# smartGarden_Per_Rev01.net
KiCad netlist of a schematic drawn in Altium Designer
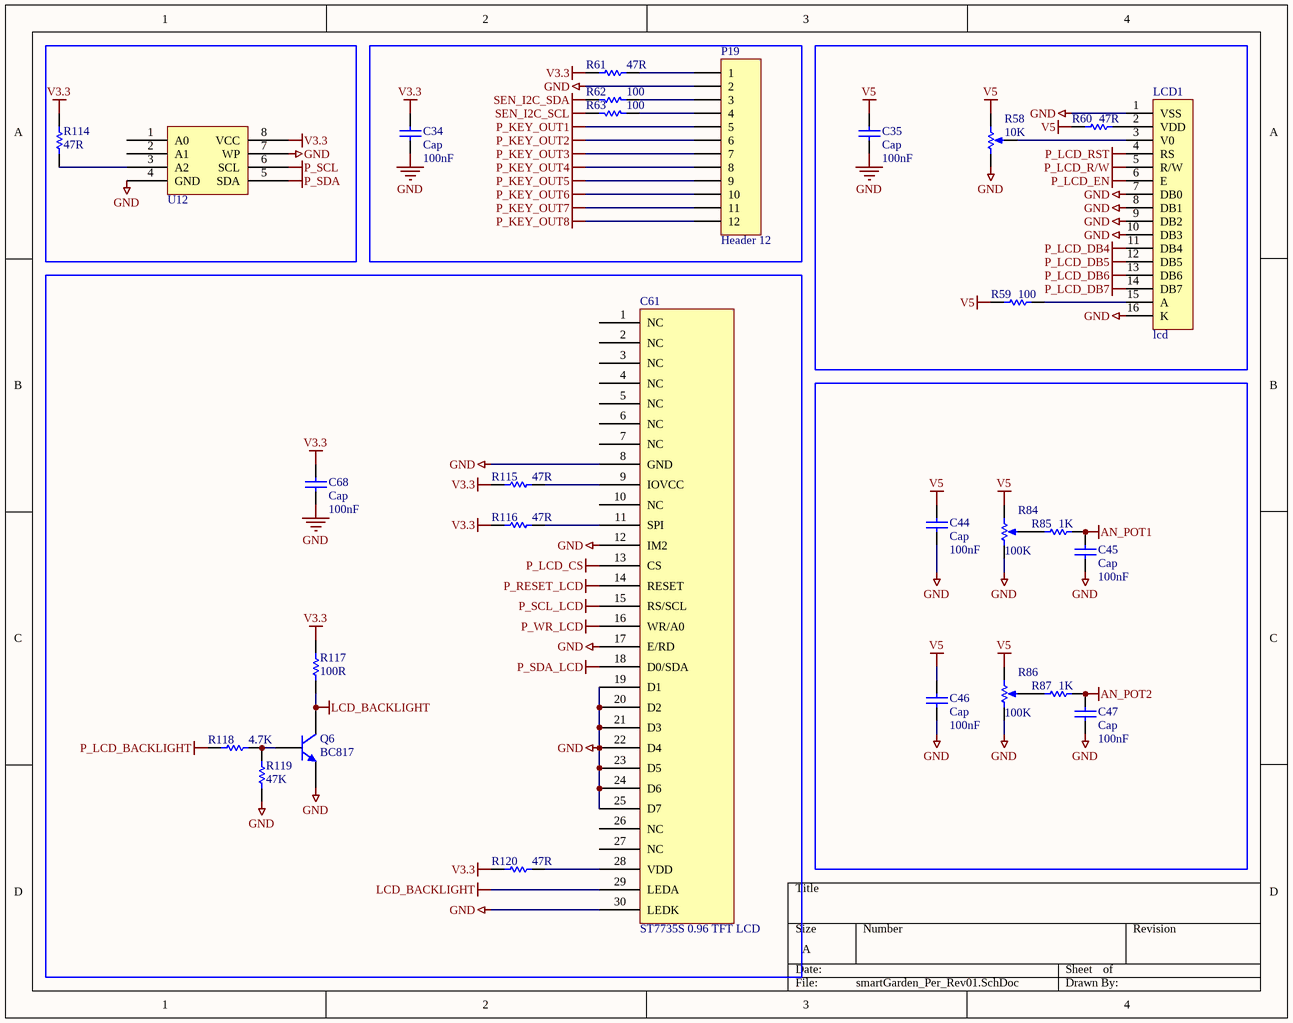
[diagram p0: smartGarden_Per_Rev01.SchDoc]

(export (version "E")
  (design (tool "Eeschema 10.0.6"))
  (components
    (comp (ref "C34")
      (value "Cap")
      (footprint "0805_smd")
      (description "Capacitor")
      (fields (field (name "ALTIUM_VALUE") "100nF") (field (name "PUBLISHER") "Altium Limited"))
      (libsource (lib "Miscellaneous Devices") (part "Cap"))
    )
    (comp (ref "C35")
      (value "Cap")
      (footprint "0805_smd")
      (description "Capacitor")
      (fields (field (name "ALTIUM_VALUE") "100nF") (field (name "PUBLISHER") "Altium Limited"))
      (libsource (lib "Miscellaneous Devices") (part "Cap"))
    )
    (comp (ref "C44")
      (value "Cap")
      (footprint "0805_smd")
      (description "Capacitor")
      (fields (field (name "ALTIUM_VALUE") "100nF") (field (name "PUBLISHER") "Altium Limited"))
      (libsource (lib "Miscellaneous Devices") (part "Cap"))
    )
    (comp (ref "C45")
      (value "Cap")
      (footprint "0805_smd")
      (description "Capacitor")
      (fields (field (name "ALTIUM_VALUE") "100nF") (field (name "PUBLISHER") "Altium Limited"))
      (libsource (lib "Miscellaneous Devices") (part "Cap"))
    )
    (comp (ref "C46")
      (value "Cap")
      (footprint "0805_smd")
      (description "Capacitor")
      (fields (field (name "ALTIUM_VALUE") "100nF") (field (name "PUBLISHER") "Altium Limited"))
      (libsource (lib "Miscellaneous Devices") (part "Cap"))
    )
    (comp (ref "C47")
      (value "Cap")
      (footprint "0805_smd")
      (description "Capacitor")
      (fields (field (name "ALTIUM_VALUE") "100nF") (field (name "PUBLISHER") "Altium Limited"))
      (libsource (lib "Miscellaneous Devices") (part "Cap"))
    )
    (comp (ref "C61")
      (value "ST7735S 0.96 TFT LCD")
      (libsource (lib "MYLib524") (part "ST7735S 0.96 TFT LCD"))
    )
    (comp (ref "C68")
      (value "Cap")
      (footprint "0805_smd")
      (description "Capacitor")
      (fields (field (name "ALTIUM_VALUE") "100nF") (field (name "PUBLISHER") "Altium Limited"))
      (libsource (lib "Miscellaneous Devices") (part "Cap"))
    )
    (comp (ref "LCD1") (value "lcd") (footprint "LCD2*16") (libsource (lib "MYLib524") (part "LCD16")))
    (comp (ref "P19")
      (value "Header 12")
      (footprint "CON12_XH")
      (description "Header, 12-Pin")
      (fields (field (name "PUBLISHER") "Altium Limited"))
      (libsource (lib "Miscellaneous Connectors") (part "Header 12"))
    )
    (comp (ref "Q6")
      (value "BC817")
      (footprint "TO-226-AA")
      (description "NPN Bipolar Transistor")
      (fields (field (name "PUBLISHER") "Altium Limited"))
      (libsource (lib "Miscellaneous Devices") (part "NPN"))
    )
    (comp (ref "R58")
      (value "10K")
      (footprint "Trimmer Pot")
      (description "Potentiometer")
      (fields (field (name "Comment") "RPot") (field (name "PUBLISHER") "Altium Limited"))
      (libsource (lib "Miscellaneous Devices") (part "RPot"))
    )
    (comp (ref "R59")
      (value "100")
      (footprint "0805_smd")
      (description "Semiconductor Resistor")
      (fields (field (name "PUBLISHER") "Altium Limited"))
      (libsource (lib "Miscellaneous Devices") (part "Res Semi"))
    )
    (comp (ref "R60")
      (value "47R")
      (footprint "0805_smd")
      (description "Semiconductor Resistor")
      (fields (field (name "PUBLISHER") "Altium Limited"))
      (libsource (lib "Miscellaneous Devices") (part "Res Semi"))
    )
    (comp (ref "R61")
      (value "47R")
      (footprint "0805_smd")
      (description "Semiconductor Resistor")
      (fields (field (name "PUBLISHER") "Altium Limited"))
      (libsource (lib "Miscellaneous Devices") (part "Res Semi"))
    )
    (comp (ref "R62")
      (value "100")
      (footprint "0805_smd")
      (description "Resistor")
      (fields (field (name "PUBLISHER") "Altium Limited"))
      (libsource (lib "Miscellaneous Devices") (part "Res1"))
    )
    (comp (ref "R63")
      (value "100")
      (footprint "0805_smd")
      (description "Resistor")
      (fields (field (name "PUBLISHER") "Altium Limited"))
      (libsource (lib "Miscellaneous Devices") (part "Res1"))
    )
    (comp (ref "R84")
      (value "100K")
      (footprint "POT_V15")
      (description "Potentiometer")
      (fields (field (name "Comment") "RPot") (field (name "PUBLISHER") "Altium Limited"))
      (libsource (lib "Miscellaneous Devices") (part "RPot"))
    )
    (comp (ref "R85")
      (value "1K")
      (footprint "0805_smd")
      (description "Semiconductor Resistor")
      (fields (field (name "PUBLISHER") "Altium Limited"))
      (libsource (lib "Miscellaneous Devices") (part "Res Semi"))
    )
    (comp (ref "R86")
      (value "100K")
      (footprint "POT_V15")
      (description "Potentiometer")
      (fields (field (name "Comment") "RPot") (field (name "PUBLISHER") "Altium Limited"))
      (libsource (lib "Miscellaneous Devices") (part "RPot"))
    )
    (comp (ref "R87")
      (value "1K")
      (footprint "0805_smd")
      (description "Semiconductor Resistor")
      (fields (field (name "PUBLISHER") "Altium Limited"))
      (libsource (lib "Miscellaneous Devices") (part "Res Semi"))
    )
    (comp (ref "R114")
      (value "47R")
      (footprint "0805_smd")
      (description "Semiconductor Resistor")
      (fields (field (name "PUBLISHER") "Altium Limited"))
      (libsource (lib "Miscellaneous Devices") (part "Res Semi"))
    )
    (comp (ref "R115")
      (value "47R")
      (footprint "0805_smd")
      (description "Semiconductor Resistor")
      (fields (field (name "PUBLISHER") "Altium Limited"))
      (libsource (lib "Miscellaneous Devices") (part "Res Semi"))
    )
    (comp (ref "R116")
      (value "47R")
      (footprint "0805_smd")
      (description "Semiconductor Resistor")
      (fields (field (name "PUBLISHER") "Altium Limited"))
      (libsource (lib "Miscellaneous Devices") (part "Res Semi"))
    )
    (comp (ref "R117")
      (value "100R")
      (footprint "0805_smd")
      (description "Semiconductor Resistor")
      (fields (field (name "PUBLISHER") "Altium Limited"))
      (libsource (lib "Miscellaneous Devices") (part "Res Semi"))
    )
    (comp (ref "R118")
      (value "4.7K")
      (footprint "0805_smd")
      (description "Semiconductor Resistor")
      (fields (field (name "PUBLISHER") "Altium Limited"))
      (libsource (lib "Miscellaneous Devices") (part "Res Semi"))
    )
    (comp (ref "R119")
      (value "47K")
      (footprint "0805_smd")
      (description "Semiconductor Resistor")
      (fields (field (name "PUBLISHER") "Altium Limited"))
      (libsource (lib "Miscellaneous Devices") (part "Res Semi"))
    )
    (comp (ref "R120")
      (value "47R")
      (footprint "0805_smd")
      (description "Semiconductor Resistor")
      (fields (field (name "PUBLISHER") "Altium Limited"))
      (libsource (lib "Miscellaneous Devices") (part "Res Semi"))
    )
    (comp (ref "U12") (value "AT24C08") (footprint "SOIC8") (libsource (lib "MYLib524") (part "AT24C08")))
  )
  (nets
    (net (code "1") (name "AN_POT1") (class "Default")
      (node (ref "C45") (pin "2") (pinfunction "2_2") (pintype "passive"))
      (node (ref "R85") (pin "1") (pinfunction "1_1") (pintype "passive"))
    )
    (net (code "2") (name "AN_POT2") (class "Default")
      (node (ref "C47") (pin "2") (pinfunction "2_2") (pintype "passive"))
      (node (ref "R87") (pin "1") (pinfunction "1_1") (pintype "passive"))
    )
    (net (code "3") (name "GND") (class "Default")
      (node (ref "C34") (pin "1") (pinfunction "1_1") (pintype "passive"))
      (node (ref "C35") (pin "1") (pinfunction "1_1") (pintype "passive"))
      (node (ref "C44") (pin "1") (pinfunction "1_1") (pintype "passive"))
      (node (ref "C45") (pin "1") (pinfunction "1_1") (pintype "passive"))
      (node (ref "C46") (pin "1") (pinfunction "1_1") (pintype "passive"))
      (node (ref "C47") (pin "1") (pinfunction "1_1") (pintype "passive"))
      (node (ref "C61") (pin "12") (pinfunction "IM2_12") (pintype "passive"))
      (node (ref "C61") (pin "17") (pinfunction "E/RD_17") (pintype "passive"))
      (node (ref "C61") (pin "19") (pinfunction "D1_19") (pintype "passive"))
      (node (ref "C61") (pin "20") (pinfunction "D2_20") (pintype "passive"))
      (node (ref "C61") (pin "21") (pinfunction "D3_21") (pintype "passive"))
      (node (ref "C61") (pin "22") (pinfunction "D4_22") (pintype "passive"))
      (node (ref "C61") (pin "23") (pinfunction "D5_23") (pintype "passive"))
      (node (ref "C61") (pin "24") (pinfunction "D6_24") (pintype "passive"))
      (node (ref "C61") (pin "25") (pinfunction "D7_25") (pintype "passive"))
      (node (ref "C61") (pin "30") (pinfunction "LEDK_30") (pintype "passive"))
      (node (ref "C61") (pin "8") (pinfunction "GND_8") (pintype "passive"))
      (node (ref "C68") (pin "1") (pinfunction "1_1") (pintype "passive"))
      (node (ref "LCD1") (pin "1") (pinfunction "VSS_1") (pintype "passive"))
      (node (ref "LCD1") (pin "10") (pinfunction "DB3_10") (pintype "passive"))
      (node (ref "LCD1") (pin "16") (pinfunction "K_16") (pintype "passive"))
      (node (ref "LCD1") (pin "7") (pinfunction "DB0_7") (pintype "passive"))
      (node (ref "LCD1") (pin "8") (pinfunction "DB1_8") (pintype "passive"))
      (node (ref "LCD1") (pin "9") (pinfunction "DB2_9") (pintype "passive"))
      (node (ref "P19") (pin "2") (pinfunction "2_2") (pintype "passive"))
      (node (ref "Q6") (pin "3") (pinfunction "E_3") (pintype "passive"))
      (node (ref "R119") (pin "2") (pinfunction "2_2") (pintype "passive"))
      (node (ref "R58") (pin "1") (pinfunction "TOP_1") (pintype "passive"))
      (node (ref "R84") (pin "1") (pinfunction "TOP_1") (pintype "passive"))
      (node (ref "R86") (pin "1") (pinfunction "TOP_1") (pintype "passive"))
      (node (ref "U12") (pin "4") (pinfunction "GND_4") (pintype "passive"))
      (node (ref "U12") (pin "7") (pinfunction "WP_7") (pintype "passive"))
    )
    (net (code "4") (name "LCD_BACKLIGHT") (class "Default")
      (node (ref "C61") (pin "29") (pinfunction "LEDA_29") (pintype "passive"))
      (node (ref "Q6") (pin "1") (pinfunction "C_1") (pintype "passive"))
      (node (ref "R117") (pin "1") (pinfunction "1_1") (pintype "passive"))
    )
    (net (code "5") (name "Net-(C61-IOVCC)") (class "Default")
      (node (ref "C61") (pin "9") (pinfunction "IOVCC_9") (pintype "passive"))
      (node (ref "R115") (pin "1") (pinfunction "1_1") (pintype "passive"))
    )
    (net (code "6") (name "Net-(C61-SPI)") (class "Default")
      (node (ref "C61") (pin "11") (pinfunction "SPI_11") (pintype "passive"))
      (node (ref "R116") (pin "1") (pinfunction "1_1") (pintype "passive"))
    )
    (net (code "7") (name "Net-(C61-VDD)") (class "Default")
      (node (ref "C61") (pin "28") (pinfunction "VDD_28") (pintype "passive"))
      (node (ref "R120") (pin "1") (pinfunction "1_1") (pintype "passive"))
    )
    (net (code "8") (name "Net-(LCD1-A)") (class "Default")
      (node (ref "LCD1") (pin "15") (pinfunction "A_15") (pintype "passive"))
      (node (ref "R59") (pin "1") (pinfunction "1_1") (pintype "passive"))
    )
    (net (code "9") (name "Net-(LCD1-V0)") (class "Default")
      (node (ref "LCD1") (pin "3") (pinfunction "V0_3") (pintype "passive"))
      (node (ref "R58") (pin "3") (pinfunction "TAP_3") (pintype "passive"))
    )
    (net (code "10") (name "Net-(LCD1-VDD)") (class "Default")
      (node (ref "LCD1") (pin "2") (pinfunction "VDD_2") (pintype "passive"))
      (node (ref "R60") (pin "1") (pinfunction "1_1") (pintype "passive"))
    )
    (net (code "11") (name "Net-(P19-Pad1)") (class "Default")
      (node (ref "P19") (pin "1") (pinfunction "1_1") (pintype "passive"))
      (node (ref "R61") (pin "1") (pinfunction "1_1") (pintype "passive"))
    )
    (net (code "12") (name "Net-(P19-Pad3)") (class "Default")
      (node (ref "P19") (pin "3") (pinfunction "3_3") (pintype "passive"))
      (node (ref "R62") (pin "2") (pinfunction "2_2") (pintype "passive"))
    )
    (net (code "13") (name "Net-(P19-Pad4)") (class "Default")
      (node (ref "P19") (pin "4") (pinfunction "4_4") (pintype "passive"))
      (node (ref "R63") (pin "2") (pinfunction "2_2") (pintype "passive"))
    )
    (net (code "14") (name "Net-(Q6-B)") (class "Default")
      (node (ref "Q6") (pin "2") (pinfunction "B_2") (pintype "passive"))
      (node (ref "R118") (pin "1") (pinfunction "1_1") (pintype "passive"))
      (node (ref "R119") (pin "1") (pinfunction "1_1") (pintype "passive"))
    )
    (net (code "15") (name "Net-(R84-TAP)") (class "Default")
      (node (ref "R84") (pin "3") (pinfunction "TAP_3") (pintype "passive"))
      (node (ref "R85") (pin "2") (pinfunction "2_2") (pintype "passive"))
    )
    (net (code "16") (name "Net-(R86-TAP)") (class "Default")
      (node (ref "R86") (pin "3") (pinfunction "TAP_3") (pintype "passive"))
      (node (ref "R87") (pin "2") (pinfunction "2_2") (pintype "passive"))
    )
    (net (code "17") (name "Net-(U12-A2)") (class "Default")
      (node (ref "R114") (pin "2") (pinfunction "2_2") (pintype "passive"))
      (node (ref "U12") (pin "3") (pinfunction "A2_3") (pintype "passive"))
    )
    (net (code "18") (name "P_KEY_OUT1") (class "Default")
      (node (ref "P19") (pin "5") (pinfunction "5_5") (pintype "passive"))
    )
    (net (code "19") (name "P_KEY_OUT2") (class "Default")
      (node (ref "P19") (pin "6") (pinfunction "6_6") (pintype "passive"))
    )
    (net (code "20") (name "P_KEY_OUT3") (class "Default")
      (node (ref "P19") (pin "7") (pinfunction "7_7") (pintype "passive"))
    )
    (net (code "21") (name "P_KEY_OUT4") (class "Default")
      (node (ref "P19") (pin "8") (pinfunction "8_8") (pintype "passive"))
    )
    (net (code "22") (name "P_KEY_OUT5") (class "Default")
      (node (ref "P19") (pin "9") (pinfunction "9_9") (pintype "passive"))
    )
    (net (code "23") (name "P_KEY_OUT6") (class "Default")
      (node (ref "P19") (pin "10") (pinfunction "10_10") (pintype "passive"))
    )
    (net (code "24") (name "P_KEY_OUT7") (class "Default")
      (node (ref "P19") (pin "11") (pinfunction "11_11") (pintype "passive"))
    )
    (net (code "25") (name "P_KEY_OUT8") (class "Default")
      (node (ref "P19") (pin "12") (pinfunction "12_12") (pintype "passive"))
    )
    (net (code "26") (name "P_LCD_BACKLIGHT") (class "Default")
      (node (ref "R118") (pin "2") (pinfunction "2_2") (pintype "passive"))
    )
    (net (code "27") (name "P_LCD_CS") (class "Default")
      (node (ref "C61") (pin "13") (pinfunction "CS_13") (pintype "passive"))
    )
    (net (code "28") (name "P_LCD_DB4") (class "Default")
      (node (ref "LCD1") (pin "11") (pinfunction "DB4_11") (pintype "passive"))
    )
    (net (code "29") (name "P_LCD_DB5") (class "Default")
      (node (ref "LCD1") (pin "12") (pinfunction "DB5_12") (pintype "passive"))
    )
    (net (code "30") (name "P_LCD_DB6") (class "Default")
      (node (ref "LCD1") (pin "13") (pinfunction "DB6_13") (pintype "passive"))
    )
    (net (code "31") (name "P_LCD_DB7") (class "Default")
      (node (ref "LCD1") (pin "14") (pinfunction "DB7_14") (pintype "passive"))
    )
    (net (code "32") (name "P_LCD_EN") (class "Default")
      (node (ref "LCD1") (pin "6") (pinfunction "E_6") (pintype "passive"))
    )
    (net (code "33") (name "P_LCD_RST") (class "Default")
      (node (ref "LCD1") (pin "4") (pinfunction "RS_4") (pintype "passive"))
    )
    (net (code "34") (name "P_LCD_R{slash}W") (class "Default")
      (node (ref "LCD1") (pin "5") (pinfunction "R/W_5") (pintype "passive"))
    )
    (net (code "35") (name "P_RESET_LCD") (class "Default")
      (node (ref "C61") (pin "14") (pinfunction "RESET_14") (pintype "passive"))
    )
    (net (code "36") (name "P_SCL") (class "Default")
      (node (ref "U12") (pin "6") (pinfunction "SCL_6") (pintype "passive"))
    )
    (net (code "37") (name "P_SCL_LCD") (class "Default")
      (node (ref "C61") (pin "15") (pinfunction "RS/SCL_15") (pintype "passive"))
    )
    (net (code "38") (name "P_SDA") (class "Default")
      (node (ref "U12") (pin "5") (pinfunction "SDA_5") (pintype "passive"))
    )
    (net (code "39") (name "P_SDA_LCD") (class "Default")
      (node (ref "C61") (pin "18") (pinfunction "D0/SDA_18") (pintype "passive"))
    )
    (net (code "40") (name "P_WR_LCD") (class "Default")
      (node (ref "C61") (pin "16") (pinfunction "WR/A0_16") (pintype "passive"))
    )
    (net (code "41") (name "SEN_I2C_SCL") (class "Default")
      (node (ref "R63") (pin "1") (pinfunction "1_1") (pintype "passive"))
    )
    (net (code "42") (name "SEN_I2C_SDA") (class "Default")
      (node (ref "R62") (pin "1") (pinfunction "1_1") (pintype "passive"))
    )
    (net (code "43") (name "V3.3") (class "Default")
      (node (ref "C34") (pin "2") (pinfunction "2_2") (pintype "passive"))
      (node (ref "C68") (pin "2") (pinfunction "2_2") (pintype "passive"))
      (node (ref "R114") (pin "1") (pinfunction "1_1") (pintype "passive"))
      (node (ref "R115") (pin "2") (pinfunction "2_2") (pintype "passive"))
      (node (ref "R116") (pin "2") (pinfunction "2_2") (pintype "passive"))
      (node (ref "R117") (pin "2") (pinfunction "2_2") (pintype "passive"))
      (node (ref "R120") (pin "2") (pinfunction "2_2") (pintype "passive"))
      (node (ref "R61") (pin "2") (pinfunction "2_2") (pintype "passive"))
      (node (ref "U12") (pin "8") (pinfunction "VCC_8") (pintype "passive"))
    )
    (net (code "44") (name "V5") (class "Default")
      (node (ref "C35") (pin "2") (pinfunction "2_2") (pintype "passive"))
      (node (ref "C44") (pin "2") (pinfunction "2_2") (pintype "passive"))
      (node (ref "C46") (pin "2") (pinfunction "2_2") (pintype "passive"))
      (node (ref "R58") (pin "2") (pinfunction "BOT_2") (pintype "passive"))
      (node (ref "R59") (pin "2") (pinfunction "2_2") (pintype "passive"))
      (node (ref "R60") (pin "2") (pinfunction "2_2") (pintype "passive"))
      (node (ref "R84") (pin "2") (pinfunction "BOT_2") (pintype "passive"))
      (node (ref "R86") (pin "2") (pinfunction "BOT_2") (pintype "passive"))
    )
    (net (code "45") (name "unconnected-(C61-NC-Pad1)") (class "Default")
      (node (ref "C61") (pin "1") (pinfunction "NC_1") (pintype "passive"))
    )
    (net (code "46") (name "unconnected-(C61-NC-Pad2)") (class "Default")
      (node (ref "C61") (pin "2") (pinfunction "NC_2") (pintype "passive"))
    )
    (net (code "47") (name "unconnected-(C61-NC-Pad3)") (class "Default")
      (node (ref "C61") (pin "3") (pinfunction "NC_3") (pintype "passive"))
    )
    (net (code "48") (name "unconnected-(C61-NC-Pad4)") (class "Default")
      (node (ref "C61") (pin "4") (pinfunction "NC_4") (pintype "passive"))
    )
    (net (code "49") (name "unconnected-(C61-NC-Pad5)") (class "Default")
      (node (ref "C61") (pin "5") (pinfunction "NC_5") (pintype "passive"))
    )
    (net (code "50") (name "unconnected-(C61-NC-Pad6)") (class "Default")
      (node (ref "C61") (pin "6") (pinfunction "NC_6") (pintype "passive"))
    )
    (net (code "51") (name "unconnected-(C61-NC-Pad7)") (class "Default")
      (node (ref "C61") (pin "7") (pinfunction "NC_7") (pintype "passive"))
    )
    (net (code "52") (name "unconnected-(C61-NC-Pad10)") (class "Default")
      (node (ref "C61") (pin "10") (pinfunction "NC_10") (pintype "passive"))
    )
    (net (code "53") (name "unconnected-(C61-NC-Pad26)") (class "Default")
      (node (ref "C61") (pin "26") (pinfunction "NC_26") (pintype "passive"))
    )
    (net (code "54") (name "unconnected-(C61-NC-Pad27)") (class "Default")
      (node (ref "C61") (pin "27") (pinfunction "NC_27") (pintype "passive"))
    )
    (net (code "55") (name "unconnected-(U12-A0-Pad1)") (class "Default")
      (node (ref "U12") (pin "1") (pinfunction "A0_1") (pintype "passive"))
    )
    (net (code "56") (name "unconnected-(U12-A1-Pad2)") (class "Default")
      (node (ref "U12") (pin "2") (pinfunction "A1_2") (pintype "passive"))
    )
  )
)
